# tick-mini-mk-2_2.net
KiCad netlist of a schematic drawn in EAGLE
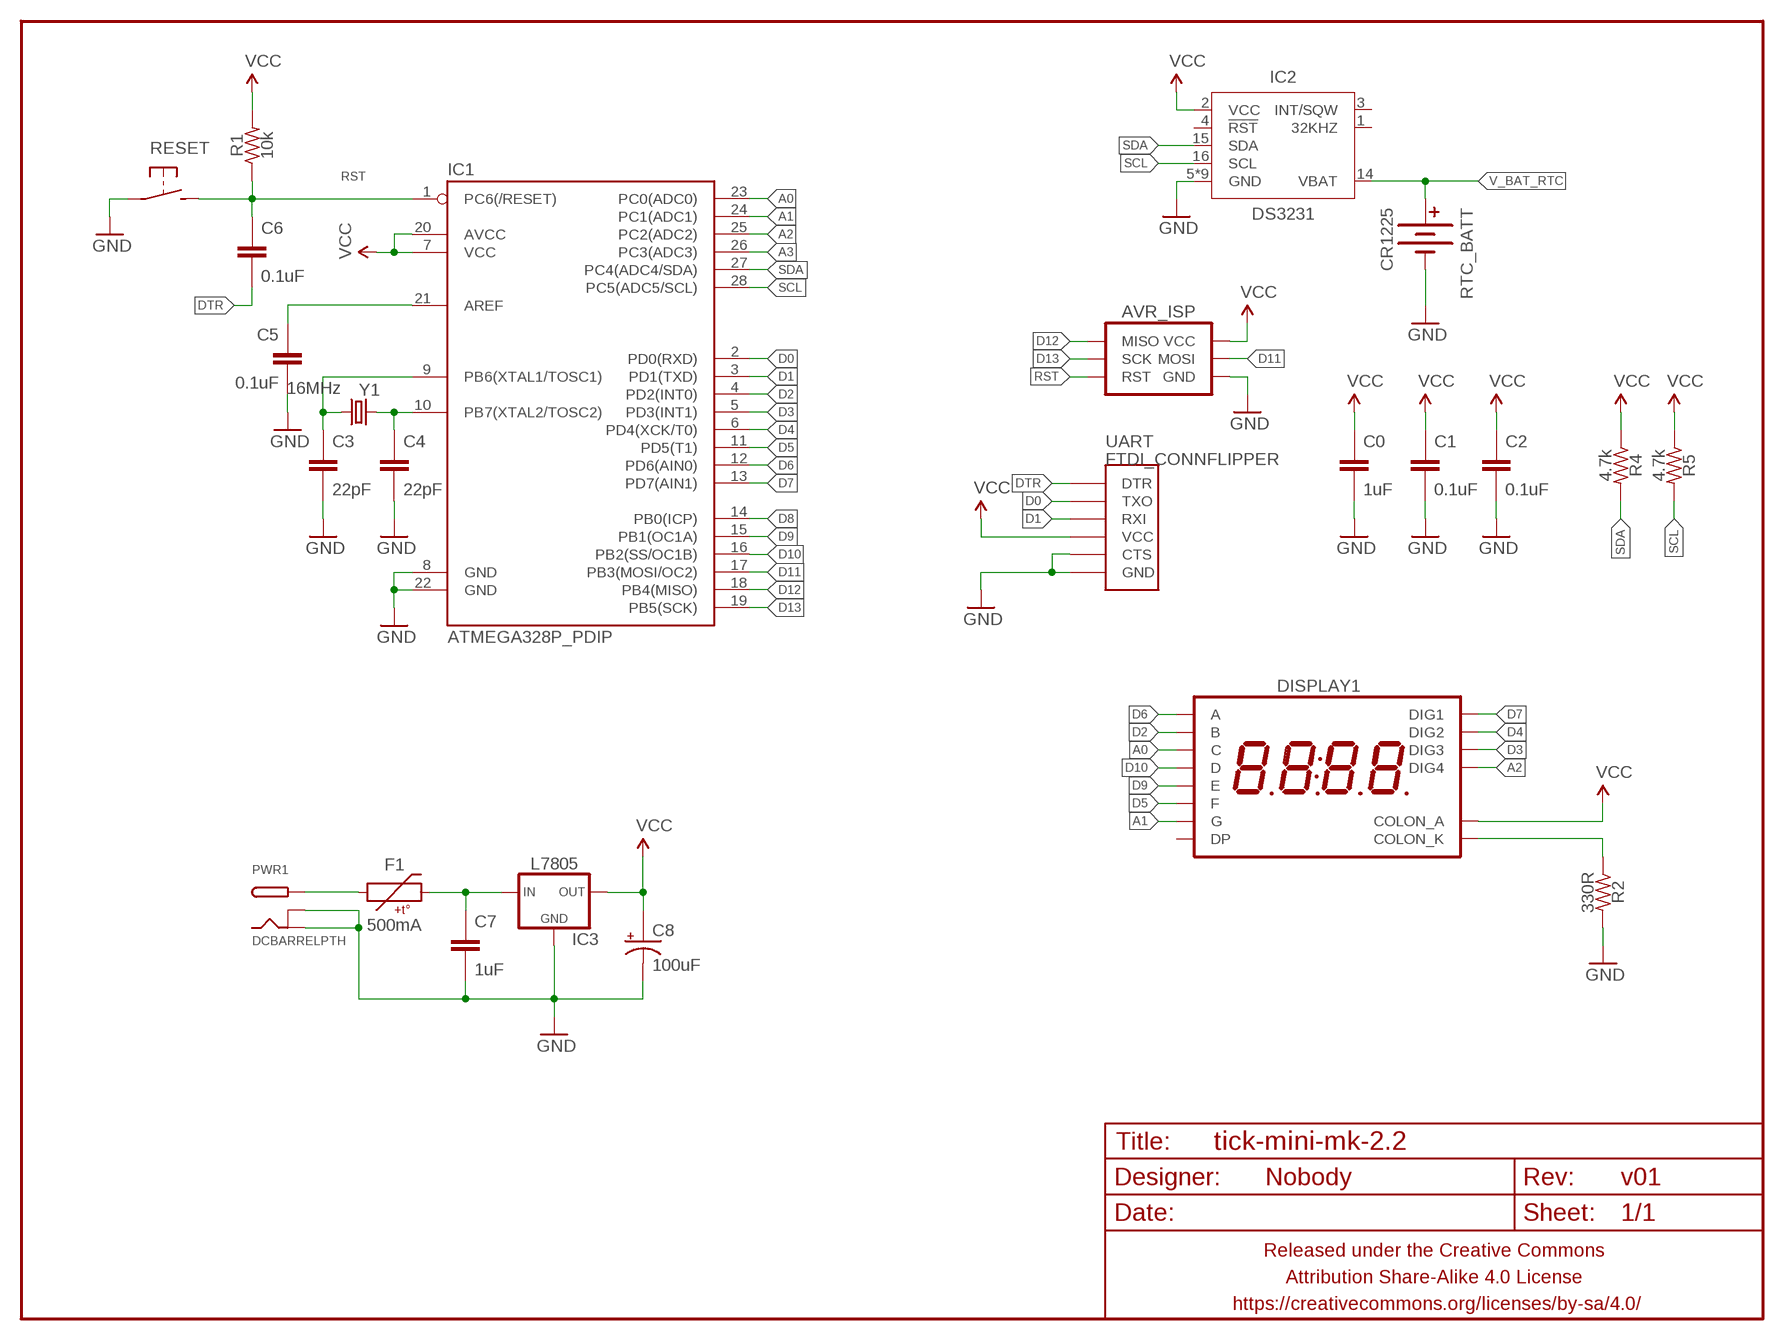
[diagram p0: schematic, sheet 1]

(export (version "E")
  (design (tool "Eeschema 10.0.6"))
  (components
    (comp (ref "AVR_ISP")
      (value "AVR_SPI_PRG_6INLINE")
      (footprint "eagle-import:AVR_MINI_PROG")
      (libsource (lib "eagle-import") (part "AVR_SPI_PRG_6INLINE"))
    )
    (comp (ref "C0")
      (value "1uF")
      (footprint "eagle-import:C025-024X044")
      (libsource (lib "eagle-import") (part "CAPACITOR-CERAMIC025-024X044"))
    )
    (comp (ref "C1")
      (value "0.1uF")
      (footprint "eagle-import:C025-024X044")
      (libsource (lib "eagle-import") (part "CAPACITOR-CERAMIC025-024X044"))
    )
    (comp (ref "C2")
      (value "0.1uF")
      (footprint "eagle-import:C025-024X044")
      (libsource (lib "eagle-import") (part "CAPACITOR-CERAMIC025-024X044"))
    )
    (comp (ref "C3")
      (value "22pF")
      (footprint "eagle-import:C025-024X044")
      (libsource (lib "eagle-import") (part "CAPACITOR-CERAMIC025-024X044"))
    )
    (comp (ref "C4")
      (value "22pF")
      (footprint "eagle-import:C025-024X044")
      (libsource (lib "eagle-import") (part "CAPACITOR-CERAMIC025-024X044"))
    )
    (comp (ref "C5")
      (value "0.1uF")
      (footprint "eagle-import:C025-024X044")
      (libsource (lib "eagle-import") (part "CAPACITOR-CERAMIC025-024X044"))
    )
    (comp (ref "C6")
      (value "0.1uF")
      (footprint "eagle-import:C025-024X044")
      (libsource (lib "eagle-import") (part "CAPACITOR-CERAMIC025-024X044"))
    )
    (comp (ref "C7")
      (value "1uF")
      (footprint "eagle-import:C025-024X044")
      (libsource (lib "eagle-import") (part "CAPACITOR-CERAMIC025-024X044"))
    )
    (comp (ref "C8")
      (value "100uF")
      (footprint "eagle-import:E2,5-5")
      (libsource (lib "eagle-import") (part "CAPACITOR-POLARIZEDE2.5-5"))
    )
    (comp (ref "DISPLAY1")
      (value "7SEG_4DIGIT_COLON14.2MM-CC-NS")
      (footprint "eagle-import:7SEG_4DIG_NS")
      (libsource (lib "eagle-import") (part "7SEG_4DIGIT_COLON14.2MM-CC-NS"))
    )
    (comp (ref "F1")
      (value "500mA")
      (footprint "eagle-import:PTC-PTH-5.08MM")
      (libsource (lib "eagle-import") (part "PTCPTH-5.08MM"))
    )
    (comp (ref "FRAME1")
      (value "FRAME-LETTERNO_PACKAGE")
      (footprint "eagle-import:DUMMY")
      (fields (field (name "DESIGNER") "Nobody"))
      (libsource (lib "eagle-import") (part "FRAME-LETTERNO_PACKAGE"))
    )
    (comp (ref "IC1")
      (value "ATMEGA328P_PDIP")
      (footprint "eagle-import:DIL28-3")
      (libsource (lib "eagle-import") (part "ATMEGA328P_PDIP"))
    )
    (comp (ref "IC2")
      (value "DS3231")
      (footprint "eagle-import:SO16W")
      (libsource (lib "eagle-import") (part "DS3231"))
    )
    (comp (ref "IC3")
      (value "L7805")
      (footprint "eagle-import:SO08")
      (libsource (lib "eagle-import") (part "V_REG_78XX"))
    )
    (comp (ref "PWR1")
      (value "DCBARRELPTH")
      (footprint "eagle-import:DCJACK_2MM_PTH")
      (libsource (lib "eagle-import") (part "DCBARRELPTH"))
    )
    (comp (ref "R1")
      (value "10k")
      (footprint "eagle-import:RESISTOR-AXIAL-PTH-7.62MM")
      (libsource (lib "eagle-import") (part "RESISTORPTH-AXIAL-7.62MM"))
    )
    (comp (ref "R2")
      (value "330R")
      (footprint "eagle-import:RESISTOR-AXIAL-PTH-7.62MM")
      (libsource (lib "eagle-import") (part "RESISTORPTH-AXIAL-7.62MM"))
    )
    (comp (ref "R4")
      (value "4.7k")
      (footprint "eagle-import:RESISTOR-AXIAL-PTH-7.62MM")
      (libsource (lib "eagle-import") (part "RESISTORPTH-AXIAL-7.62MM"))
    )
    (comp (ref "R5")
      (value "4.7k")
      (footprint "eagle-import:RESISTOR-AXIAL-PTH-7.62MM")
      (libsource (lib "eagle-import") (part "RESISTORPTH-AXIAL-7.62MM"))
    )
    (comp (ref "RESET")
      (value "SPST-NO-TACT3MM-PTH-SMALL-PADS")
      (footprint "eagle-import:DTS-3-SMALL-PADS")
      (libsource (lib "eagle-import") (part "SPST-NO-TACT3MM-PTH-SMALL-PADS"))
    )
    (comp (ref "RTC_BATT")
      (value "CR1225")
      (footprint "eagle-import:BATTCON_12MM")
      (libsource (lib "eagle-import") (part "BATTERY12MM"))
    )
    (comp (ref "UART")
      (value "FTDI_CONNFLIPPER")
      (footprint "eagle-import:FTDI_CONN_FLIP")
      (libsource (lib "eagle-import") (part "FTDI_CONNFLIPPER"))
    )
    (comp (ref "Y1")
      (value "16MHz")
      (footprint "eagle-import:HC49U-V")
      (libsource (lib "eagle-import") (part "CRYSTALHC49UV"))
    )
  )
  (nets
    (net (code "1") (name "A0") (class "Default")
      (node (ref "DISPLAY1") (pin "P$4") (pinfunction "C_P$4") (pintype "passive"))
      (node (ref "IC1") (pin "23") (pinfunction "PC0(ADC0)_23") (pintype "bidirectional"))
    )
    (net (code "2") (name "A1") (class "Default")
      (node (ref "DISPLAY1") (pin "P$5") (pinfunction "G_P$5") (pintype "passive"))
      (node (ref "IC1") (pin "24") (pinfunction "PC1(ADC1)_24") (pintype "bidirectional"))
    )
    (net (code "3") (name "A2") (class "Default")
      (node (ref "DISPLAY1") (pin "P$6") (pinfunction "DIG4_P$6") (pintype "passive"))
      (node (ref "IC1") (pin "25") (pinfunction "PC2(ADC2)_25") (pintype "bidirectional"))
    )
    (net (code "4") (name "A3") (class "Default")
      (node (ref "IC1") (pin "26") (pinfunction "PC3(ADC3)_26") (pintype "bidirectional"))
    )
    (net (code "5") (name "D0") (class "Default")
      (node (ref "IC1") (pin "2") (pinfunction "PD0(RXD)_2") (pintype "bidirectional"))
      (node (ref "UART") (pin "TXO") (pinfunction "TXO_TXO") (pintype "bidirectional"))
    )
    (net (code "6") (name "D1") (class "Default")
      (node (ref "IC1") (pin "3") (pinfunction "PD1(TXD)_3") (pintype "bidirectional"))
      (node (ref "UART") (pin "RXI") (pinfunction "RXI_RXI") (pintype "bidirectional"))
    )
    (net (code "7") (name "D2") (class "Default")
      (node (ref "DISPLAY1") (pin "P$9") (pinfunction "B_P$9") (pintype "passive"))
      (node (ref "IC1") (pin "4") (pinfunction "PD2(INT0)_4") (pintype "bidirectional"))
    )
    (net (code "8") (name "D3") (class "Default")
      (node (ref "DISPLAY1") (pin "P$10") (pinfunction "DIG3_P$10") (pintype "passive"))
      (node (ref "IC1") (pin "5") (pinfunction "PD3(INT1)_5") (pintype "bidirectional"))
    )
    (net (code "9") (name "D4") (class "Default")
      (node (ref "DISPLAY1") (pin "P$11") (pinfunction "DIG2_P$11") (pintype "passive"))
      (node (ref "IC1") (pin "6") (pinfunction "PD4(XCK/T0)_6") (pintype "bidirectional"))
    )
    (net (code "10") (name "D5") (class "Default")
      (node (ref "DISPLAY1") (pin "P$12") (pinfunction "F_P$12") (pintype "passive"))
      (node (ref "IC1") (pin "11") (pinfunction "PD5(T1)_11") (pintype "bidirectional"))
    )
    (net (code "11") (name "D6") (class "Default")
      (node (ref "DISPLAY1") (pin "P$13") (pinfunction "A_P$13") (pintype "passive"))
      (node (ref "IC1") (pin "12") (pinfunction "PD6(AIN0)_12") (pintype "bidirectional"))
    )
    (net (code "12") (name "D7") (class "Default")
      (node (ref "DISPLAY1") (pin "P$14") (pinfunction "DIG1_P$14") (pintype "passive"))
      (node (ref "IC1") (pin "13") (pinfunction "PD7(AIN1)_13") (pintype "bidirectional"))
    )
    (net (code "13") (name "D8") (class "Default")
      (node (ref "IC1") (pin "14") (pinfunction "PB0(ICP)_14") (pintype "bidirectional"))
    )
    (net (code "14") (name "D9") (class "Default")
      (node (ref "DISPLAY1") (pin "P$1") (pinfunction "E_P$1") (pintype "passive"))
      (node (ref "IC1") (pin "15") (pinfunction "PB1(OC1A)_15") (pintype "bidirectional"))
    )
    (net (code "15") (name "D10") (class "Default")
      (node (ref "DISPLAY1") (pin "P$2") (pinfunction "D_P$2") (pintype "passive"))
      (node (ref "IC1") (pin "16") (pinfunction "PB2(SS/OC1B)_16") (pintype "bidirectional"))
    )
    (net (code "16") (name "D11") (class "Default")
      (node (ref "AVR_ISP") (pin "4") (pinfunction "MOSI_4") (pintype "passive"))
      (node (ref "IC1") (pin "17") (pinfunction "PB3(MOSI/OC2)_17") (pintype "bidirectional"))
    )
    (net (code "17") (name "D12") (class "Default")
      (node (ref "AVR_ISP") (pin "1") (pinfunction "MISO_1") (pintype "passive"))
      (node (ref "IC1") (pin "18") (pinfunction "PB4(MISO)_18") (pintype "bidirectional"))
    )
    (net (code "18") (name "D13") (class "Default")
      (node (ref "AVR_ISP") (pin "3") (pinfunction "SCK_3") (pintype "passive"))
      (node (ref "IC1") (pin "19") (pinfunction "PB5(SCK)_19") (pintype "bidirectional"))
    )
    (net (code "19") (name "DTR") (class "Default")
      (node (ref "C6") (pin "2") (pinfunction "2_2") (pintype "passive"))
      (node (ref "UART") (pin "DTR") (pinfunction "DTR_DTR") (pintype "bidirectional"))
    )
    (net (code "20") (name "GND") (class "Default")
      (node (ref "AVR_ISP") (pin "6") (pinfunction "GND_6") (pintype "passive"))
      (node (ref "C0") (pin "2") (pinfunction "2_2") (pintype "passive"))
      (node (ref "C1") (pin "2") (pinfunction "2_2") (pintype "passive"))
      (node (ref "C2") (pin "2") (pinfunction "2_2") (pintype "passive"))
      (node (ref "C3") (pin "2") (pinfunction "2_2") (pintype "passive"))
      (node (ref "C4") (pin "2") (pinfunction "2_2") (pintype "passive"))
      (node (ref "C5") (pin "2") (pinfunction "2_2") (pintype "passive"))
      (node (ref "C7") (pin "2") (pinfunction "2_2") (pintype "passive"))
      (node (ref "C8") (pin "-") (pinfunction "-_-") (pintype "passive"))
      (node (ref "IC1") (pin "22") (pinfunction "GND_22") (pintype "bidirectional"))
      (node (ref "IC1") (pin "8") (pinfunction "GND_8") (pintype "bidirectional"))
      (node (ref "IC2") (pin "10") (pinfunction "GND_10") (pintype "bidirectional"))
      (node (ref "IC2") (pin "11") (pinfunction "GND_11") (pintype "bidirectional"))
      (node (ref "IC2") (pin "12") (pinfunction "GND_12") (pintype "bidirectional"))
      (node (ref "IC2") (pin "13") (pinfunction "GND_13") (pintype "bidirectional"))
      (node (ref "IC2") (pin "5") (pinfunction "GND_5") (pintype "bidirectional"))
      (node (ref "IC2") (pin "6") (pinfunction "GND_6") (pintype "bidirectional"))
      (node (ref "IC2") (pin "7") (pinfunction "GND_7") (pintype "bidirectional"))
      (node (ref "IC2") (pin "8") (pinfunction "GND_8") (pintype "bidirectional"))
      (node (ref "IC2") (pin "9") (pinfunction "GND_9") (pintype "bidirectional"))
      (node (ref "IC3") (pin "2") (pinfunction "GND_2") (pintype "bidirectional"))
      (node (ref "IC3") (pin "3") (pinfunction "GND_3") (pintype "bidirectional"))
      (node (ref "IC3") (pin "4") (pinfunction "GND_4") (pintype "bidirectional"))
      (node (ref "IC3") (pin "5") (pinfunction "GND_5") (pintype "bidirectional"))
      (node (ref "IC3") (pin "6") (pinfunction "GND_6") (pintype "bidirectional"))
      (node (ref "IC3") (pin "7") (pinfunction "GND_7") (pintype "bidirectional"))
      (node (ref "PWR1") (pin "BRK") (pinfunction "BRK_BRK") (pintype "bidirectional"))
      (node (ref "PWR1") (pin "GND") (pinfunction "GND_GND") (pintype "bidirectional"))
      (node (ref "R2") (pin "P$2") (pinfunction "2_P$2") (pintype "passive"))
      (node (ref "RESET") (pin "1") (pinfunction "1_1") (pintype "passive"))
      (node (ref "RTC_BATT") (pin "GND") (pinfunction "-_GND") (pintype "power_in"))
      (node (ref "UART") (pin "CTS") (pinfunction "CTS_CTS") (pintype "bidirectional"))
      (node (ref "UART") (pin "GND") (pinfunction "GND_GND") (pintype "bidirectional"))
    )
    (net (code "21") (name "Net-(DISPLAY1-COLON_K)") (class "Default")
      (node (ref "DISPLAY1") (pin "P$7") (pinfunction "COLON_K_P$7") (pintype "passive"))
      (node (ref "R2") (pin "P$1") (pinfunction "1_P$1") (pintype "passive"))
    )
    (net (code "22") (name "Net-(F1-1)") (class "Default")
      (node (ref "F1") (pin "P$1") (pinfunction "1_P$1") (pintype "passive"))
      (node (ref "PWR1") (pin "PWR") (pinfunction "PWR_PWR") (pintype "bidirectional"))
    )
    (net (code "23") (name "Net-(F1-2)") (class "Default")
      (node (ref "C7") (pin "1") (pinfunction "1_1") (pintype "passive"))
      (node (ref "F1") (pin "P$2") (pinfunction "2_P$2") (pintype "passive"))
      (node (ref "IC3") (pin "8") (pinfunction "IN_8") (pintype "bidirectional"))
    )
    (net (code "24") (name "Net-(IC1-AREF)") (class "Default")
      (node (ref "C5") (pin "1") (pinfunction "1_1") (pintype "passive"))
      (node (ref "IC1") (pin "21") (pinfunction "AREF_21") (pintype "bidirectional"))
    )
    (net (code "25") (name "Net-(IC1-PB6(XTAL1{slash}TOSC1))") (class "Default")
      (node (ref "C3") (pin "1") (pinfunction "1_1") (pintype "passive"))
      (node (ref "IC1") (pin "9") (pinfunction "PB6(XTAL1/TOSC1)_9") (pintype "bidirectional"))
      (node (ref "Y1") (pin "2") (pinfunction "2_2") (pintype "passive"))
    )
    (net (code "26") (name "Net-(IC1-PB7(XTAL2{slash}TOSC2))") (class "Default")
      (node (ref "C4") (pin "1") (pinfunction "1_1") (pintype "passive"))
      (node (ref "IC1") (pin "10") (pinfunction "PB7(XTAL2/TOSC2)_10") (pintype "bidirectional"))
      (node (ref "Y1") (pin "1") (pinfunction "1_1") (pintype "passive"))
    )
    (net (code "27") (name "RST") (class "Default")
      (node (ref "AVR_ISP") (pin "5") (pinfunction "RST_5") (pintype "passive"))
      (node (ref "C6") (pin "1") (pinfunction "1_1") (pintype "passive"))
      (node (ref "IC1") (pin "1") (pinfunction "PC6(/RESET)_1") (pintype "bidirectional"))
      (node (ref "R1") (pin "P$1") (pinfunction "1_P$1") (pintype "passive"))
      (node (ref "RESET") (pin "2") (pinfunction "2_2") (pintype "passive"))
    )
    (net (code "28") (name "SCL") (class "Default")
      (node (ref "IC1") (pin "28") (pinfunction "PC5(ADC5/SCL)_28") (pintype "bidirectional"))
      (node (ref "IC2") (pin "16") (pinfunction "SCL_16") (pintype "bidirectional"))
      (node (ref "R5") (pin "P$2") (pinfunction "2_P$2") (pintype "passive"))
    )
    (net (code "29") (name "SDA") (class "Default")
      (node (ref "IC1") (pin "27") (pinfunction "PC4(ADC4/SDA)_27") (pintype "bidirectional"))
      (node (ref "IC2") (pin "15") (pinfunction "SDA_15") (pintype "bidirectional"))
      (node (ref "R4") (pin "P$2") (pinfunction "2_P$2") (pintype "passive"))
    )
    (net (code "30") (name "VCC") (class "Default")
      (node (ref "AVR_ISP") (pin "2") (pinfunction "VCC_2") (pintype "passive"))
      (node (ref "C0") (pin "1") (pinfunction "1_1") (pintype "passive"))
      (node (ref "C1") (pin "1") (pinfunction "1_1") (pintype "passive"))
      (node (ref "C2") (pin "1") (pinfunction "1_1") (pintype "passive"))
      (node (ref "C8") (pin "+") (pinfunction "+_+") (pintype "passive"))
      (node (ref "DISPLAY1") (pin "P$8") (pinfunction "COLON_A_P$8") (pintype "passive"))
      (node (ref "IC1") (pin "20") (pinfunction "AVCC_20") (pintype "bidirectional"))
      (node (ref "IC1") (pin "7") (pinfunction "VCC_7") (pintype "bidirectional"))
      (node (ref "IC2") (pin "2") (pinfunction "VCC_2") (pintype "bidirectional"))
      (node (ref "IC3") (pin "1") (pinfunction "OUT_1") (pintype "bidirectional"))
      (node (ref "R1") (pin "P$2") (pinfunction "2_P$2") (pintype "passive"))
      (node (ref "R4") (pin "P$1") (pinfunction "1_P$1") (pintype "passive"))
      (node (ref "R5") (pin "P$1") (pinfunction "1_P$1") (pintype "passive"))
      (node (ref "UART") (pin "VCC") (pinfunction "VCC_VCC") (pintype "bidirectional"))
    )
    (net (code "31") (name "V_BAT_RTC") (class "Default")
      (node (ref "IC2") (pin "14") (pinfunction "VBAT_14") (pintype "bidirectional"))
      (node (ref "RTC_BATT") (pin "PWR@1") (pinfunction "+_PWR@1") (pintype "power_in"))
    )
    (net (code "32") (name "unconnected-(DISPLAY1-DP-PadP$3)") (class "Default")
      (node (ref "DISPLAY1") (pin "P$3") (pinfunction "DP_P$3") (pintype "passive"))
    )
    (net (code "33") (name "unconnected-(IC2-32KHZ-Pad1)") (class "Default")
      (node (ref "IC2") (pin "1") (pinfunction "32KHZ_1") (pintype "bidirectional"))
    )
    (net (code "34") (name "unconnected-(IC2-INT{slash}SQW-Pad3)") (class "Default")
      (node (ref "IC2") (pin "3") (pinfunction "INT/SQW_3") (pintype "bidirectional"))
    )
    (net (code "35") (name "unconnected-(IC2-~{RST}-Pad4)") (class "Default")
      (node (ref "IC2") (pin "4") (pinfunction "~{RST}_4") (pintype "bidirectional"))
    )
  )
)
